# DBG.net
KiCad netlist of a schematic drawn in Altium Designer
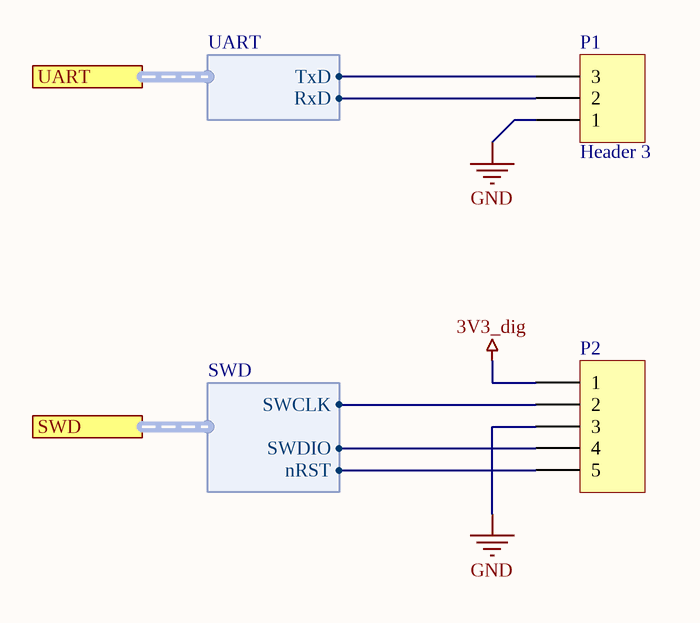
[diagram p0: DBG.SchDoc]

(export (version "E")
  (design (tool "Eeschema 10.0.6"))
  (components
    (comp (ref "P1")
      (value "Header 3")
      (footprint "HEADER1X3H Male")
      (description "Header, 3-Pin")
      (fields (field (name "PUBLISHER") "Altium Limited"))
      (libsource (lib "_Connectors") (part "Header 3"))
    )
    (comp (ref "P2")
      (value "Header 5")
      (footprint "HDR1X5")
      (description "Header, 5-Pin")
      (fields (field (name "PUBLISHER") "Altium Limited"))
      (libsource (lib "_Connectors") (part "Header 5"))
    )
  )
  (nets
    (net (code "3") (name "/RxD") (class "Default")
      (node (ref "P1") (pin "2") (pinfunction "2_2") (pintype "passive"))
    )
    (net (code "4") (name "/SWCLK") (class "Default")
      (node (ref "P2") (pin "2") (pinfunction "2_2") (pintype "passive"))
    )
    (net (code "5") (name "/SWDIO") (class "Default")
      (node (ref "P2") (pin "4") (pinfunction "4_4") (pintype "passive"))
    )
    (net (code "6") (name "/TxD") (class "Default")
      (node (ref "P1") (pin "3") (pinfunction "3_3") (pintype "passive"))
    )
    (net (code "7") (name "/nRST") (class "Default")
      (node (ref "P2") (pin "5") (pinfunction "5_5") (pintype "passive"))
    )
    (net (code "10") (name "3V3_dig") (class "Default")
      (node (ref "P2") (pin "1") (pinfunction "1_1") (pintype "passive"))
    )
    (net (code "11") (name "GND") (class "Default")
      (node (ref "P1") (pin "1") (pinfunction "1_1") (pintype "passive"))
      (node (ref "P2") (pin "3") (pinfunction "3_3") (pintype "passive"))
    )
  )
)
